# Dcdc_12V0_6V5.net
KiCad netlist of a schematic drawn in Altium Designer
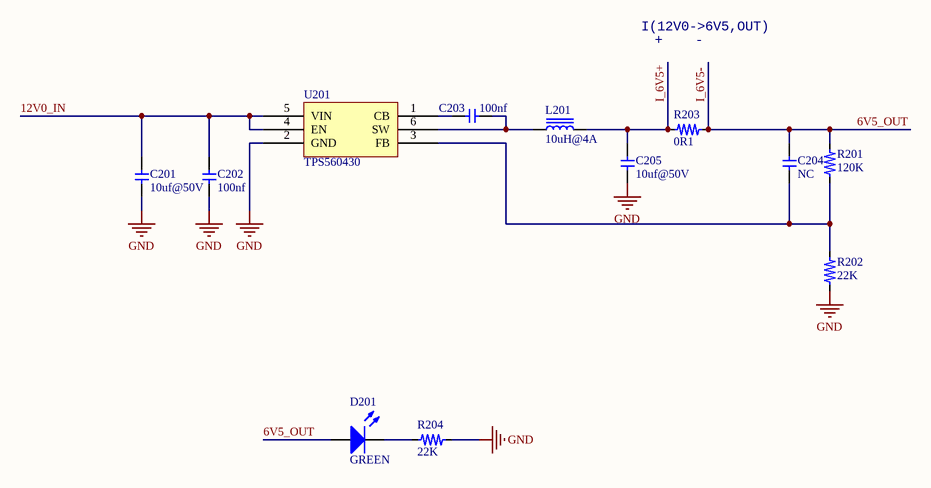
[diagram p0: Dcdc.12V0.+6V5.SchDoc]

(export (version "E")
  (design (tool "Eeschema 10.0.6"))
  (components
    (comp (ref "C201")
      (value "10uf@50V")
      (footprint "C1210")
      (fields (field (name "Comment") "Cap"))
      (libsource (lib "carrot_lib") (part "Cap"))
    )
    (comp (ref "C202")
      (value "100nf")
      (footprint "C0603")
      (fields (field (name "Comment") "Cap"))
      (libsource (lib "carrot_lib") (part "Cap"))
    )
    (comp (ref "C203")
      (value "100nf")
      (footprint "C0603")
      (fields (field (name "Comment") "Cap"))
      (libsource (lib "carrot_lib") (part "Cap"))
    )
    (comp (ref "C204")
      (value "NC")
      (footprint "C0603")
      (fields (field (name "Comment") "Cap"))
      (libsource (lib "carrot_lib") (part "Cap"))
    )
    (comp (ref "C205")
      (value "10uf@50V")
      (footprint "C1210")
      (fields (field (name "Comment") "Cap"))
      (libsource (lib "carrot_lib") (part "Cap"))
    )
    (comp (ref "D201")
      (value "GREEN")
      (footprint "LED0603")
      (fields (field (name "Comment") "LED"))
      (libsource (lib "carrot_lib") (part "LED"))
    )
    (comp (ref "L201")
      (value "10uH@4A")
      (footprint "L06063")
      (description "Magnetic-Core Inductor")
      (fields (field (name "Comment") "Inductor Iron"))
      (libsource (lib "carrot_lib") (part "Inductor Iron"))
    )
    (comp (ref "R201")
      (value "120K")
      (footprint "R0603")
      (description "电阻")
      (fields (field (name "Comment") "Res"))
      (libsource (lib "carrot_lib") (part "Res"))
    )
    (comp (ref "R202")
      (value "22K")
      (footprint "R0603")
      (description "电阻")
      (fields (field (name "Comment") "Res"))
      (libsource (lib "carrot_lib") (part "Res"))
    )
    (comp (ref "R203")
      (value "0R1")
      (footprint "R1206")
      (description "电阻")
      (fields (field (name "Comment") "Res"))
      (libsource (lib "carrot_lib") (part "Res"))
    )
    (comp (ref "R204")
      (value "22K")
      (footprint "R0603")
      (description "电阻")
      (fields (field (name "Comment") "Res"))
      (libsource (lib "carrot_lib") (part "Res"))
    )
    (comp (ref "U201")
      (value "TPS560430")
      (footprint "TPS560430-SOT23-6")
      (description "TPS560430 SIMPLE SWITCHER® 4-V to 36-V, 600-mA Synchronous Step-Down Converter")
      (libsource (lib "carrot_lib") (part "TPS560430"))
    )
  )
  (nets
    (net (code "1") (name "/6V5_OUT") (class "Default")
      (node (ref "C204") (pin "1") (pinfunction "1_1") (pintype "passive"))
      (node (ref "D201") (pin "1") (pinfunction "A_1") (pintype "passive"))
      (node (ref "R201") (pin "2") (pinfunction "2_2") (pintype "passive"))
      (node (ref "R203") (pin "2") (pinfunction "2_2") (pintype "passive"))
    )
    (net (code "2") (name "/12V0_IN") (class "Default")
      (node (ref "C201") (pin "2") (pinfunction "2_2") (pintype "passive"))
      (node (ref "C202") (pin "2") (pinfunction "2_2") (pintype "passive"))
      (node (ref "U201") (pin "4") (pinfunction "EN_4") (pintype "passive"))
      (node (ref "U201") (pin "5") (pinfunction "VIN_5") (pintype "passive"))
    )
    (net (code "3") (name "/I_6V5+") (class "Default")
      (node (ref "C205") (pin "2") (pinfunction "2_2") (pintype "passive"))
      (node (ref "L201") (pin "2") (pinfunction "2_2") (pintype "passive"))
      (node (ref "R203") (pin "1") (pinfunction "1_1") (pintype "passive"))
    )
    (net (code "4") (name "GND") (class "Default")
      (node (ref "C201") (pin "1") (pinfunction "1_1") (pintype "passive"))
      (node (ref "C202") (pin "1") (pinfunction "1_1") (pintype "passive"))
      (node (ref "C205") (pin "1") (pinfunction "1_1") (pintype "passive"))
      (node (ref "R202") (pin "1") (pinfunction "1_1") (pintype "passive"))
      (node (ref "R204") (pin "1") (pinfunction "1_1") (pintype "passive"))
      (node (ref "U201") (pin "2") (pinfunction "GND_2") (pintype "passive"))
    )
    (net (code "5") (name "Net-(D201-K)") (class "Default")
      (node (ref "D201") (pin "2") (pinfunction "K_2") (pintype "passive"))
      (node (ref "R204") (pin "2") (pinfunction "2_2") (pintype "passive"))
    )
    (net (code "6") (name "Net-(U201-CB)") (class "Default")
      (node (ref "C203") (pin "2") (pinfunction "2_2") (pintype "passive"))
      (node (ref "U201") (pin "1") (pinfunction "CB_1") (pintype "passive"))
    )
    (net (code "7") (name "Net-(U201-FB)") (class "Default")
      (node (ref "C204") (pin "2") (pinfunction "2_2") (pintype "passive"))
      (node (ref "R201") (pin "1") (pinfunction "1_1") (pintype "passive"))
      (node (ref "R202") (pin "2") (pinfunction "2_2") (pintype "passive"))
      (node (ref "U201") (pin "3") (pinfunction "FB_3") (pintype "passive"))
    )
    (net (code "8") (name "Net-(U201-SW)") (class "Default")
      (node (ref "C203") (pin "1") (pinfunction "1_1") (pintype "passive"))
      (node (ref "L201") (pin "1") (pinfunction "1_1") (pintype "passive"))
      (node (ref "U201") (pin "6") (pinfunction "SW_6") (pintype "passive"))
    )
  )
)
